# IoT_Greenhouse_V1_0_A_-_Esp32.net
KiCad netlist of a schematic drawn in Altium Designer
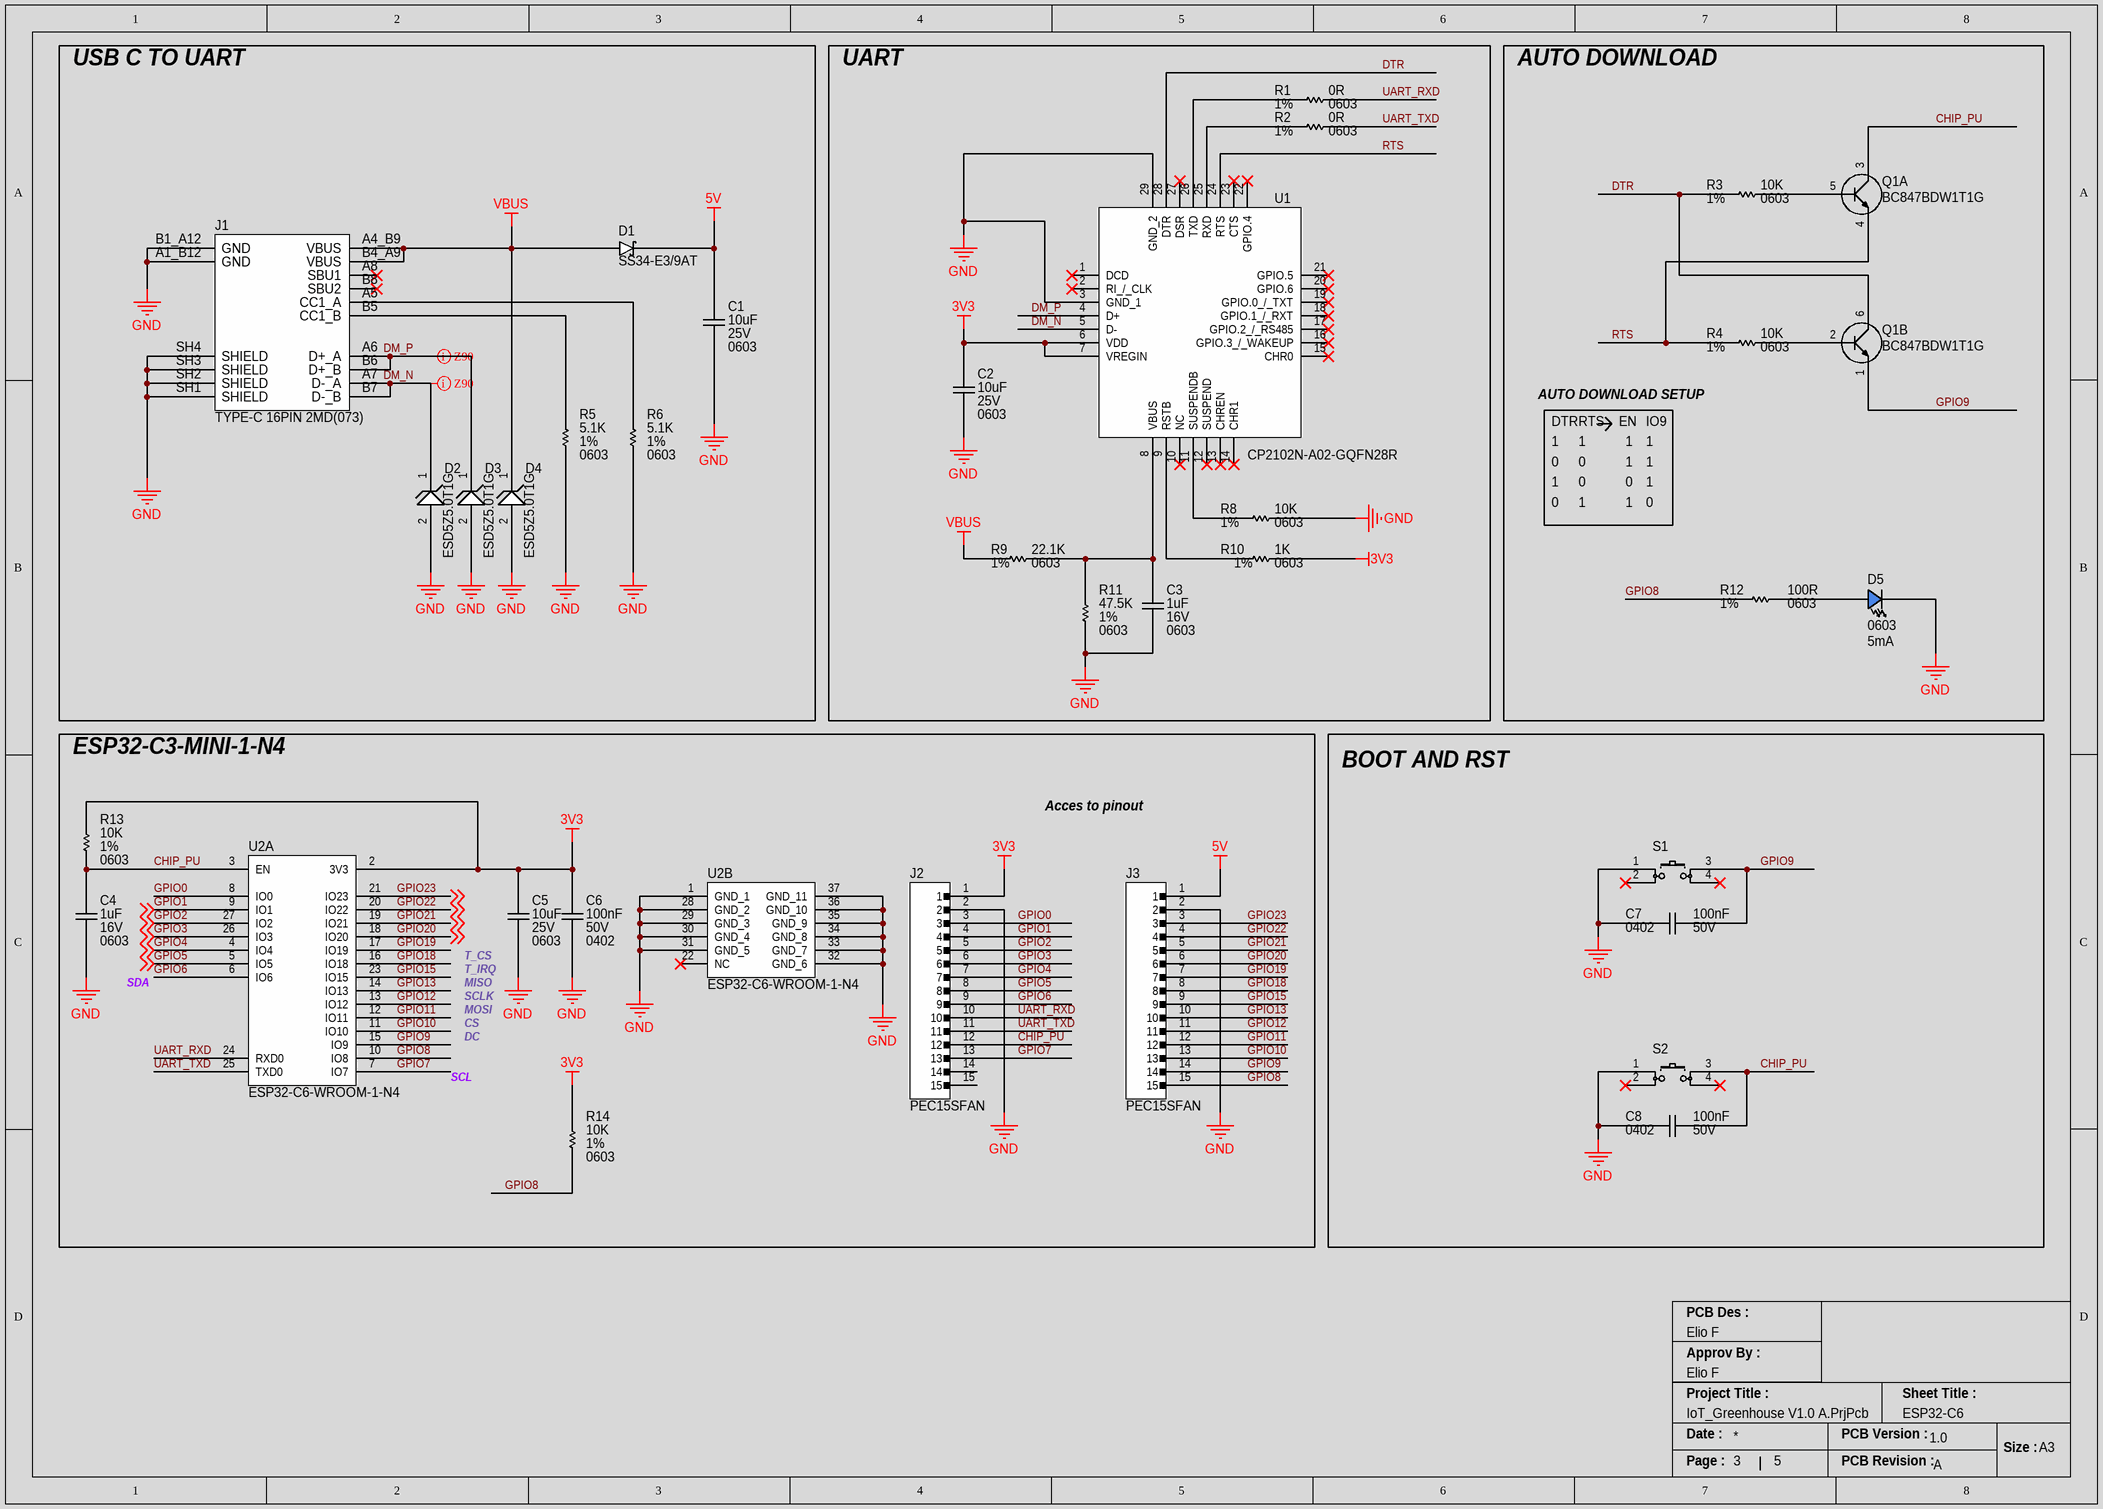
[diagram p0: IoT_Greenhouse V1.0 A - Esp32.SchDoc]

(export (version "E")
  (design (tool "Eeschema 10.0.6"))
  (components
    (comp (ref "C1")
      (value "GRM188R61E106MA73D")
      (footprint "CAP_0603_CAPC1608X08N")
      (description "Multilayer Ceramic Capacitor, 10 uF, 25 V, ± 20%, X5R, 0603 [1608 Metric]")
      (fields
        (field (name "MANUFACTURER") "Murata")
        (field (name "TOLERANCE") "20%")
        (field (name "CASE/PACKAGE") "0603")
        (field (name "CAPACITANCE") "10uF")
        (field (name "VOLTAGE RATING") "25V")
      )
      (libsource (lib "Electronic Devices_LIB") (part "CAP_10UF_25V_X5R_0603"))
    )
    (comp (ref "C2")
      (value "GRM188R61E106MA73D")
      (footprint "CAP_0603_CAPC1608X08N")
      (description "Multilayer Ceramic Capacitor, 10 uF, 25 V, ± 20%, X5R, 0603 [1608 Metric]")
      (fields
        (field (name "MANUFACTURER") "Murata")
        (field (name "TOLERANCE") "20%")
        (field (name "CASE/PACKAGE") "0603")
        (field (name "CAPACITANCE") "10uF")
        (field (name "VOLTAGE RATING") "25V")
      )
      (libsource (lib "Electronic Devices_LIB") (part "CAP_10UF_25V_X5R_0603"))
    )
    (comp (ref "C3")
      (value "CL10A105KO8NNNC")
      (footprint "CAP_0603_CAPC1608X08N")
      (description "CAP CER 1UF 16V X5R 0603")
      (fields
        (field (name "MANUFACTURER") "Samsung")
        (field (name "TOLERANCE") "10%")
        (field (name "VOLTAGE RATING") "16V")
        (field (name "CAPACITANCE") "1uF")
        (field (name "CASE/PACKAGE") "0603")
      )
      (libsource (lib "Electronic Devices_LIB") (part "CAP_1UF_16V_X5R_0603"))
    )
    (comp (ref "C4")
      (value "CL10A105KO8NNNC")
      (footprint "CAP_0603_CAPC1608X08N")
      (description "CAP CER 1UF 16V X5R 0603")
      (fields
        (field (name "MANUFACTURER") "Samsung")
        (field (name "TOLERANCE") "10%")
        (field (name "VOLTAGE RATING") "16V")
        (field (name "CAPACITANCE") "1uF")
        (field (name "CASE/PACKAGE") "0603")
      )
      (libsource (lib "Electronic Devices_LIB") (part "CAP_1UF_16V_X5R_0603"))
    )
    (comp (ref "C5")
      (value "GRM188R61E106MA73D")
      (footprint "CAP_0603_CAPC1608X08N")
      (description "Multilayer Ceramic Capacitor, 10 uF, 25 V, ± 20%, X5R, 0603 [1608 Metric]")
      (fields
        (field (name "MANUFACTURER") "Murata")
        (field (name "TOLERANCE") "20%")
        (field (name "CASE/PACKAGE") "0603")
        (field (name "CAPACITANCE") "10uF")
        (field (name "VOLTAGE RATING") "25V")
      )
      (libsource (lib "Electronic Devices_LIB") (part "CAP_10UF_25V_X5R_0603"))
    )
    (comp (ref "C6")
      (value "GRM155R71H104KE14D")
      (footprint "CAP_0402_CAPC1005X05N")
      (description "Multilayer Ceramic Capacitor, 0.1 uF, 16 V, ± 10%, X7R, 0402 [1005 Metric]")
      (fields
        (field (name "MANUFACTURER") "Murata")
        (field (name "TOLERANCE") "10%")
        (field (name "VOLTAGE RATING") "50V")
        (field (name "CAPACITANCE") "100nF")
        (field (name "CASE/PACKAGE") "0402")
      )
      (libsource (lib "Electronic Devices_LIB") (part "CAP_100NF_50V_X7R_0402"))
    )
    (comp (ref "C7")
      (value "GRM155R71H104KE14D")
      (footprint "CAP_0402_CAPC1005X05N")
      (description "Multilayer Ceramic Capacitor, 0.1 uF, 16 V, ± 10%, X7R, 0402 [1005 Metric]")
      (fields
        (field (name "MANUFACTURER") "Murata")
        (field (name "TOLERANCE") "10%")
        (field (name "VOLTAGE RATING") "50V")
        (field (name "CAPACITANCE") "100nF")
        (field (name "CASE/PACKAGE") "0402")
      )
      (libsource (lib "Electronic Devices_LIB") (part "CAP_100NF_50V_X7R_0402"))
    )
    (comp (ref "C8")
      (value "GRM155R71H104KE14D")
      (footprint "CAP_0402_CAPC1005X05N")
      (description "Multilayer Ceramic Capacitor, 0.1 uF, 16 V, ± 10%, X7R, 0402 [1005 Metric]")
      (fields
        (field (name "MANUFACTURER") "Murata")
        (field (name "TOLERANCE") "10%")
        (field (name "VOLTAGE RATING") "50V")
        (field (name "CAPACITANCE") "100nF")
        (field (name "CASE/PACKAGE") "0402")
      )
      (libsource (lib "Electronic Devices_LIB") (part "CAP_100NF_50V_X7R_0402"))
    )
    (comp (ref "D1")
      (value "SS34-E3/9AT")
      (footprint "DIO_Vishay_SMC_MFG")
      (description "Rectifier Diode, schottky, 40V V(Rrm), do-214Ab / Smc")
      (fields (field (name "MANUFACTURER") "Vishay Semiconductors"))
      (libsource (lib "Electronic Devices_LIB") (part "DIO_SCTKY_40V_3A"))
    )
    (comp (ref "D2")
      (value "ESD5Z5.0T1G")
      (footprint "SOD523_SODFL1608X70N")
      (description "ESD5Z Series 6.2 V 80 pF 5 Vrwm TVS and ESD Protection Diodes - SOD-523")
      (fields (field (name "MANUFACTURER") "ON Semiconductor"))
      (libsource (lib "Electronic Devices_LIB") (part "DIO_TVS_5V_ESD5Z5.0T1G"))
    )
    (comp (ref "D3")
      (value "ESD5Z5.0T1G")
      (footprint "SOD523_SODFL1608X70N")
      (description "ESD5Z Series 6.2 V 80 pF 5 Vrwm TVS and ESD Protection Diodes - SOD-523")
      (fields (field (name "MANUFACTURER") "ON Semiconductor"))
      (libsource (lib "Electronic Devices_LIB") (part "DIO_TVS_5V_ESD5Z5.0T1G"))
    )
    (comp (ref "D4")
      (value "ESD5Z5.0T1G")
      (footprint "SOD523_SODFL1608X70N")
      (description "ESD5Z Series 6.2 V 80 pF 5 Vrwm TVS and ESD Protection Diodes - SOD-523")
      (fields (field (name "MANUFACTURER") "ON Semiconductor"))
      (libsource (lib "Electronic Devices_LIB") (part "DIO_TVS_5V_ESD5Z5.0T1G"))
    )
    (comp (ref "D5")
      (value "LTST-C193TBKT-5A")
      (footprint "LED_0603-BLUE-0.75mm")
      (description "LED Uni-Color Blue 468nm 2-Pin Chip LED T/R")
      (fields
        (field (name "MANUFACTURER") "Vishay Lite-On")
        (field (name "CASE CODE (IMPERIAL)") "0603")
        (field (name "TEST CURRENT") "5mA")
      )
      (libsource (lib "Electronic Devices_LIB") (part "LED_DIO_BLUE_5mA_0603"))
    )
    (comp (ref "J1")
      (value "TYPE-C 16PIN 2MD(073)")
      (footprint "CONN_USB_C_16P")
      (description "5A 1 Surface Mount 16P Female -25℃~+85℃ Type-C SMD USB Connectors ROHS")
      (fields (field (name "MANUFACTURER") "SHOU HAN"))
      (libsource (lib "Electronic Devices_LIB") (part "CONN_USB_TYPEC_2.0_16P_TYPE-C 16PIN 2MD(073)"))
    )
    (comp (ref "J2")
      (value "PEC15SFAN")
      (footprint "HEADER_MALE_15P")
      (description "CONN HEADER .100 SINGL STR 15POS")
      (fields (field (name "MANUFACTURER") "Sullins"))
      (libsource (lib "Electronic Devices_LIB") (part "CONN_HEADER_MALE_15P_2.54mm"))
    )
    (comp (ref "J3")
      (value "PEC15SFAN")
      (footprint "HEADER_MALE_15P")
      (description "CONN HEADER .100 SINGL STR 15POS")
      (fields (field (name "MANUFACTURER") "Sullins"))
      (libsource (lib "Electronic Devices_LIB") (part "CONN_HEADER_MALE_15P_2.54mm"))
    )
    (comp (ref "Q1")
      (value "BC847BDW1T1G")
      (footprint "TRANS_BJT_SOT65P210X110-6N")
      (description "ON Semi BC847BDW1T1G Dual NPN Bipolar Transistor; 0.1 A; 45 V; 6-Pin SC-88")
      (fields (field (name "MANUFACTURER") "ON Semiconductor"))
      (libsource (lib "Electronic Devices_LIB") (part "TRANS_BIPOLAR_NPN_BC847BDW1T1G"))
    )
    (comp (ref "R1")
      (value "RC0603FR-070RL")
      (footprint "RES_0603_RESC1608X04N")
      (description "RC Series 0603 0.1 W 0 Ohm Jumper Surface Mount Thick Film Chip Resistor")
      (fields
        (field (name "MANUFACTURER") "Yageo")
        (field (name "TOLERANCE") "1%")
        (field (name "RESISTANCE") "0R")
        (field (name "CASE CODE (IMPERIAL)") "0603")
      )
      (libsource (lib "Electronic Devices_LIB") (part "RES_0R_1%_100mW_0603"))
    )
    (comp (ref "R2")
      (value "RC0603FR-070RL")
      (footprint "RES_0603_RESC1608X04N")
      (description "RC Series 0603 0.1 W 0 Ohm Jumper Surface Mount Thick Film Chip Resistor")
      (fields
        (field (name "MANUFACTURER") "Yageo")
        (field (name "TOLERANCE") "1%")
        (field (name "RESISTANCE") "0R")
        (field (name "CASE CODE (IMPERIAL)") "0603")
      )
      (libsource (lib "Electronic Devices_LIB") (part "RES_0R_1%_100mW_0603"))
    )
    (comp (ref "R3")
      (value "AC0603FR-1010KL")
      (footprint "RES_0603_RESC1608X04N")
      (description "Chip Resistor Automotive Grade Thick Film 0603 10kOhm 1% Paper T/R")
      (fields
        (field (name "MANUFACTURER") "Yageo")
        (field (name "RESISTANCE") "10K")
        (field (name "TOLERANCE") "1%")
        (field (name "CASE/PACKAGE") "0603")
      )
      (libsource (lib "Electronic Devices_LIB") (part "RES_10K_1%_100mW_0603"))
    )
    (comp (ref "R4")
      (value "AC0603FR-1010KL")
      (footprint "RES_0603_RESC1608X04N")
      (description "Chip Resistor Automotive Grade Thick Film 0603 10kOhm 1% Paper T/R")
      (fields
        (field (name "MANUFACTURER") "Yageo")
        (field (name "RESISTANCE") "10K")
        (field (name "TOLERANCE") "1%")
        (field (name "CASE/PACKAGE") "0603")
      )
      (libsource (lib "Electronic Devices_LIB") (part "RES_10K_1%_100mW_0603"))
    )
    (comp (ref "R5")
      (value "RC0603FR-075K1L")
      (footprint "RES_0603_RESC1608X04N")
      (description "SMD Chip Resistor, 5.1 kOhm, ± 1%, 100 mW, 0603 [1608 Metric], Thick Film, General Purpose")
      (fields
        (field (name "MANUFACTURER") "Yageo")
        (field (name "TOLERANCE") "1%")
        (field (name "RESISTANCE") "5.1K")
        (field (name "CASE/PACKAGE") "0603")
      )
      (libsource (lib "Electronic Devices_LIB") (part "RES_5.1K_1%_100mW_0603"))
    )
    (comp (ref "R6")
      (value "RC0603FR-075K1L")
      (footprint "RES_0603_RESC1608X04N")
      (description "SMD Chip Resistor, 5.1 kOhm, ± 1%, 100 mW, 0603 [1608 Metric], Thick Film, General Purpose")
      (fields
        (field (name "MANUFACTURER") "Yageo")
        (field (name "TOLERANCE") "1%")
        (field (name "RESISTANCE") "5.1K")
        (field (name "CASE/PACKAGE") "0603")
      )
      (libsource (lib "Electronic Devices_LIB") (part "RES_5.1K_1%_100mW_0603"))
    )
    (comp (ref "R8")
      (value "AC0603FR-1010KL")
      (footprint "RES_0603_RESC1608X04N")
      (description "Chip Resistor Automotive Grade Thick Film 0603 10kOhm 1% Paper T/R")
      (fields
        (field (name "MANUFACTURER") "Yageo")
        (field (name "RESISTANCE") "10K")
        (field (name "TOLERANCE") "1%")
        (field (name "CASE/PACKAGE") "0603")
      )
      (libsource (lib "Electronic Devices_LIB") (part "RES_10K_1%_100mW_0603"))
    )
    (comp (ref "R9")
      (value "RC0603FR-0722K1L")
      (footprint "RES_0603_RESC1608X04N")
      (description "SMD Chip Resistor, 22.1 kOhm, ± 1%, 100 mW, 0603 [1608 Metric], Thick Film, General Purpose")
      (fields
        (field (name "MANUFACTURER") "Yageo")
        (field (name "RESISTANCE") "22.1K")
        (field (name "TOLERANCE") "1%")
        (field (name "CASE/PACKAGE") "0603")
      )
      (libsource (lib "Electronic Devices_LIB") (part "RES_22.1K_1%_100mW_0603"))
    )
    (comp (ref "R10")
      (value "AC0603FR-101KL")
      (footprint "RES_0603_RESC1608X04N")
      (description "Chip Resistor Automotive Grade Thick Film 0603 1kOhm 1% Paper T/R")
      (fields
        (field (name "MANUFACTURER") "Yageo")
        (field (name "RESISTANCE") "1K")
        (field (name "TOLERANCE") "1%")
        (field (name "CASE/PACKAGE") "0603")
      )
      (libsource (lib "Electronic Devices_LIB") (part "RES_1K_1%_100mW_0603"))
    )
    (comp (ref "R11")
      (value "AC0603FR-0747K5L")
      (footprint "RES_0603_RESC1608X04N")
      (description "SMD Chip Resistor, 47.5 kOhm, ± 1%, 100 mW, 0603 [1608 Metric], Thick Film, General Purpose")
      (fields
        (field (name "MANUFACTURER") "Yageo")
        (field (name "TOLERANCE") "1%")
        (field (name "RESISTANCE") "47.5K")
        (field (name "CASE/PACKAGE") "0603")
      )
      (libsource (lib "Electronic Devices_LIB") (part "RES_47.5K_1%_100mW_0603"))
    )
    (comp (ref "R12")
      (value "ERJ3EKF1000V")
      (footprint "CAP_0603_CAPC1608X08N")
      (description "Res Thick Film 0603 100 Ohm 1% 1/10W ±100ppm/°C Molded SMD Punched Carrier T/R")
      (fields
        (field (name "MANUFACTURER") "Panasonic")
        (field (name "CASE CODE (IMPERIAL)") "0603")
        (field (name "TOLERANCE") "1%")
        (field (name "RESISTANCE") "100R")
      )
      (libsource (lib "Electronic Devices_LIB") (part "RES_100R_1%_100MW_0603"))
    )
    (comp (ref "R13")
      (value "AC0603FR-1010KL")
      (footprint "RES_0603_RESC1608X04N")
      (description "Chip Resistor Automotive Grade Thick Film 0603 10kOhm 1% Paper T/R")
      (fields
        (field (name "MANUFACTURER") "Yageo")
        (field (name "RESISTANCE") "10K")
        (field (name "TOLERANCE") "1%")
        (field (name "CASE/PACKAGE") "0603")
      )
      (libsource (lib "Electronic Devices_LIB") (part "RES_10K_1%_100mW_0603"))
    )
    (comp (ref "R14")
      (value "AC0603FR-1010KL")
      (footprint "RES_0603_RESC1608X04N")
      (description "Chip Resistor Automotive Grade Thick Film 0603 10kOhm 1% Paper T/R")
      (fields
        (field (name "MANUFACTURER") "Yageo")
        (field (name "RESISTANCE") "10K")
        (field (name "TOLERANCE") "1%")
        (field (name "CASE/PACKAGE") "0603")
      )
      (libsource (lib "Electronic Devices_LIB") (part "RES_10K_1%_100mW_0603"))
    )
    (comp (ref "S1")
      (value "PTS526SK15SMTR2LFS")
      (footprint "SWT_NO_PTS526SK15SMTR2LFS")
      (description "Switch Tactile N.O. SPST Round Button Gull Wing 0.05A 12VDC 200000Cycles 2.55N SMD T/R")
      (fields (field (name "MANUFACTURER") "ITT C&K"))
      (libsource (lib "Electronic Devices_LIB") (part "SWITCH_NO_SPST_0.05A"))
    )
    (comp (ref "S2")
      (value "PTS526SK15SMTR2LFS")
      (footprint "SWT_NO_PTS526SK15SMTR2LFS")
      (description "Switch Tactile N.O. SPST Round Button Gull Wing 0.05A 12VDC 200000Cycles 2.55N SMD T/R")
      (fields (field (name "MANUFACTURER") "ITT C&K"))
      (libsource (lib "Electronic Devices_LIB") (part "SWITCH_NO_SPST_0.05A"))
    )
    (comp (ref "U1")
      (value "CP2102N-A02-GQFN28R")
      (footprint "IC_BRIDGE_UART_QFN50P500X500X80-29N-D")
      (description "Full Speed USB to UART Bridge USB 2.0 3.3V T/R Automotive 28-Pin QFN EP")
      (fields (field (name "MANUFACTURER") "Silicon Labs"))
      (libsource (lib "Electronic Devices_LIB") (part "IC_BRIDGE_UART_CP2102N-A02-GQFN28R"))
    )
    (comp (ref "U2")
      (value "ESP32-C6-WROOM-1-N4")
      (footprint "IC_MODULE_ESP32C6WROOM1N4")
      (description "ESP32-C6-WROOM-1-N4 Engineering Module - 4 MB Quad SPI Flash")
      (fields (field (name "MANUFACTURER") "Espressif Systems"))
      (libsource (lib "Electronic Devices_LIB") (part "IC_MODULE_ESP32-C6-WROOM-1-N4"))
    )
  )
  (nets
    (net (code "1") (name "/CHIP_PU") (class "Default")
      (node (ref "C4") (pin "2") (pinfunction "2_2") (pintype "passive"))
      (node (ref "C8") (pin "1") (pinfunction "1_1") (pintype "passive"))
      (node (ref "J2") (pin "12") (pinfunction "12_12") (pintype "passive"))
      (node (ref "Q1") (pin "3") (pinfunction "COLLECTOR_1_3") (pintype "passive"))
      (node (ref "R13") (pin "2") (pinfunction "2_2") (pintype "passive"))
      (node (ref "S2") (pin "3") (pinfunction "NO1_3") (pintype "passive"))
      (node (ref "U2") (pin "3") (pinfunction "EN_3") (pintype "passive"))
    )
    (net (code "2") (name "/DM_N") (class "Default")
      (node (ref "D2") (pin "1") (pinfunction "K_1") (pintype "passive"))
      (node (ref "J1") (pin "A7") (pinfunction "D-_A_A7") (pintype "passive"))
      (node (ref "J1") (pin "B7") (pinfunction "D-_B_B7") (pintype "passive"))
      (node (ref "U1") (pin "5") (pinfunction "D-_5") (pintype "passive"))
    )
    (net (code "3") (name "/DM_P") (class "Default")
      (node (ref "D3") (pin "1") (pinfunction "K_1") (pintype "passive"))
      (node (ref "J1") (pin "A6") (pinfunction "D+_A_A6") (pintype "passive"))
      (node (ref "J1") (pin "B6") (pinfunction "D+_B_B6") (pintype "passive"))
      (node (ref "U1") (pin "4") (pinfunction "D+_4") (pintype "passive"))
    )
    (net (code "4") (name "/DTR") (class "Default")
      (node (ref "Q1") (pin "6") (pinfunction "COLLECTOR_2_6") (pintype "passive"))
      (node (ref "R3") (pin "2") (pinfunction "2_2") (pintype "passive"))
      (node (ref "U1") (pin "28") (pinfunction "DTR_28") (pintype "passive"))
    )
    (net (code "5") (name "/GPIO0") (class "Default")
      (node (ref "J2") (pin "3") (pinfunction "3_3") (pintype "passive"))
      (node (ref "U2") (pin "8") (pinfunction "IO0_8") (pintype "passive"))
    )
    (net (code "6") (name "/GPIO1") (class "Default")
      (node (ref "J2") (pin "4") (pinfunction "4_4") (pintype "passive"))
      (node (ref "J2") (pin "5") (pinfunction "5_5") (pintype "passive"))
      (node (ref "J2") (pin "6") (pinfunction "6_6") (pintype "passive"))
      (node (ref "J2") (pin "7") (pinfunction "7_7") (pintype "passive"))
      (node (ref "J2") (pin "8") (pinfunction "8_8") (pintype "passive"))
      (node (ref "J3") (pin "3") (pinfunction "3_3") (pintype "passive"))
      (node (ref "J3") (pin "4") (pinfunction "4_4") (pintype "passive"))
      (node (ref "J3") (pin "5") (pinfunction "5_5") (pintype "passive"))
      (node (ref "J3") (pin "6") (pinfunction "6_6") (pintype "passive"))
      (node (ref "U2") (pin "18") (pinfunction "IO20_18") (pintype "passive"))
      (node (ref "U2") (pin "19") (pinfunction "IO21_19") (pintype "passive"))
      (node (ref "U2") (pin "20") (pinfunction "IO22_20") (pintype "passive"))
      (node (ref "U2") (pin "21") (pinfunction "IO23_21") (pintype "passive"))
      (node (ref "U2") (pin "26") (pinfunction "IO3_26") (pintype "passive"))
      (node (ref "U2") (pin "27") (pinfunction "IO2_27") (pintype "passive"))
      (node (ref "U2") (pin "4") (pinfunction "IO4_4") (pintype "passive"))
      (node (ref "U2") (pin "5") (pinfunction "IO5_5") (pintype "passive"))
      (node (ref "U2") (pin "9") (pinfunction "IO1_9") (pintype "passive"))
    )
    (net (code "7") (name "/GPIO6") (class "Default")
      (node (ref "J2") (pin "9") (pinfunction "9_9") (pintype "passive"))
      (node (ref "U2") (pin "6") (pinfunction "IO6_6") (pintype "passive"))
    )
    (net (code "8") (name "/GPIO7") (class "Default")
      (node (ref "J2") (pin "13") (pinfunction "13_13") (pintype "passive"))
      (node (ref "U2") (pin "7") (pinfunction "IO7_7") (pintype "passive"))
    )
    (net (code "9") (name "/GPIO8") (class "Default")
      (node (ref "J3") (pin "15") (pinfunction "15_15") (pintype "passive"))
      (node (ref "R12") (pin "1") (pinfunction "1_1") (pintype "passive"))
      (node (ref "R14") (pin "2") (pinfunction "2_2") (pintype "passive"))
      (node (ref "U2") (pin "10") (pinfunction "IO8_10") (pintype "passive"))
    )
    (net (code "10") (name "/GPIO9") (class "Default")
      (node (ref "C7") (pin "1") (pinfunction "1_1") (pintype "passive"))
      (node (ref "J3") (pin "14") (pinfunction "14_14") (pintype "passive"))
      (node (ref "Q1") (pin "1") (pinfunction "EMITTER_2_1") (pintype "passive"))
      (node (ref "S1") (pin "3") (pinfunction "NO1_3") (pintype "passive"))
      (node (ref "U2") (pin "15") (pinfunction "IO9_15") (pintype "passive"))
    )
    (net (code "11") (name "/GPIO10") (class "Default")
      (node (ref "J3") (pin "13") (pinfunction "13_13") (pintype "passive"))
      (node (ref "U2") (pin "11") (pinfunction "IO10_11") (pintype "passive"))
    )
    (net (code "12") (name "/GPIO11") (class "Default")
      (node (ref "J3") (pin "12") (pinfunction "12_12") (pintype "passive"))
      (node (ref "U2") (pin "12") (pinfunction "IO11_12") (pintype "passive"))
    )
    (net (code "13") (name "/GPIO12") (class "Default")
      (node (ref "J3") (pin "11") (pinfunction "11_11") (pintype "passive"))
      (node (ref "U2") (pin "13") (pinfunction "IO12_13") (pintype "passive"))
    )
    (net (code "14") (name "/GPIO13") (class "Default")
      (node (ref "J3") (pin "10") (pinfunction "10_10") (pintype "passive"))
      (node (ref "U2") (pin "14") (pinfunction "IO13_14") (pintype "passive"))
    )
    (net (code "15") (name "/GPIO15") (class "Default")
      (node (ref "J3") (pin "9") (pinfunction "9_9") (pintype "passive"))
      (node (ref "U2") (pin "23") (pinfunction "IO15_23") (pintype "passive"))
    )
    (net (code "16") (name "/GPIO18") (class "Default")
      (node (ref "J3") (pin "8") (pinfunction "8_8") (pintype "passive"))
      (node (ref "U2") (pin "16") (pinfunction "IO18_16") (pintype "passive"))
    )
    (net (code "17") (name "/GPIO19") (class "Default")
      (node (ref "J3") (pin "7") (pinfunction "7_7") (pintype "passive"))
      (node (ref "U2") (pin "17") (pinfunction "IO19_17") (pintype "passive"))
    )
    (net (code "18") (name "/RTS") (class "Default")
      (node (ref "Q1") (pin "4") (pinfunction "EMITTER_1_4") (pintype "passive"))
      (node (ref "R4") (pin "2") (pinfunction "2_2") (pintype "passive"))
      (node (ref "U1") (pin "24") (pinfunction "RTS_24") (pintype "passive"))
    )
    (net (code "19") (name "/UART_RXD") (class "Default")
      (node (ref "J2") (pin "10") (pinfunction "10_10") (pintype "passive"))
      (node (ref "R1") (pin "1") (pinfunction "1_1") (pintype "passive"))
      (node (ref "U2") (pin "24") (pinfunction "RXD0_24") (pintype "passive"))
    )
    (net (code "20") (name "/UART_TXD") (class "Default")
      (node (ref "J2") (pin "11") (pinfunction "11_11") (pintype "passive"))
      (node (ref "R2") (pin "1") (pinfunction "1_1") (pintype "passive"))
      (node (ref "U2") (pin "25") (pinfunction "TXD0_25") (pintype "passive"))
    )
    (net (code "21") (name "3V3") (class "Default")
      (node (ref "C2") (pin "2") (pinfunction "2_2") (pintype "passive"))
      (node (ref "C5") (pin "2") (pinfunction "2_2") (pintype "passive"))
      (node (ref "C6") (pin "2") (pinfunction "2_2") (pintype "passive"))
      (node (ref "J2") (pin "1") (pinfunction "1_1") (pintype "passive"))
      (node (ref "R10") (pin "2") (pinfunction "2_2") (pintype "passive"))
      (node (ref "R13") (pin "1") (pinfunction "1_1") (pintype "passive"))
      (node (ref "R14") (pin "1") (pinfunction "1_1") (pintype "passive"))
      (node (ref "U1") (pin "6") (pinfunction "VDD_6") (pintype "passive"))
      (node (ref "U1") (pin "7") (pinfunction "VREGIN_7") (pintype "passive"))
      (node (ref "U2") (pin "2") (pinfunction "3V3_2") (pintype "passive"))
    )
    (net (code "22") (name "5V") (class "Default")
      (node (ref "C1") (pin "2") (pinfunction "2_2") (pintype "passive"))
      (node (ref "D1") (pin "1") (pinfunction "K_1") (pintype "passive"))
      (node (ref "J3") (pin "1") (pinfunction "1_1") (pintype "passive"))
    )
    (net (code "23") (name "GND") (class "Default")
      (node (ref "C1") (pin "1") (pinfunction "1_1") (pintype "passive"))
      (node (ref "C2") (pin "1") (pinfunction "1_1") (pintype "passive"))
      (node (ref "C3") (pin "1") (pinfunction "1_1") (pintype "passive"))
      (node (ref "C4") (pin "1") (pinfunction "1_1") (pintype "passive"))
      (node (ref "C5") (pin "1") (pinfunction "1_1") (pintype "passive"))
      (node (ref "C6") (pin "1") (pinfunction "1_1") (pintype "passive"))
      (node (ref "C7") (pin "2") (pinfunction "2_2") (pintype "passive"))
      (node (ref "C8") (pin "2") (pinfunction "2_2") (pintype "passive"))
      (node (ref "D2") (pin "2") (pinfunction "A_2") (pintype "passive"))
      (node (ref "D3") (pin "2") (pinfunction "A_2") (pintype "passive"))
      (node (ref "D4") (pin "2") (pinfunction "A_2") (pintype "passive"))
      (node (ref "D5") (pin "1") (pinfunction "C_1") (pintype "passive"))
      (node (ref "J1") (pin "A1_B12") (pinfunction "GND_A1_B12") (pintype "power_in"))
      (node (ref "J1") (pin "B1_A12") (pinfunction "GND_B1_A12") (pintype "power_in"))
      (node (ref "J1") (pin "SH1") (pinfunction "SHIELD_SH1") (pintype "passive"))
      (node (ref "J1") (pin "SH2") (pinfunction "SHIELD_SH2") (pintype "passive"))
      (node (ref "J1") (pin "SH3") (pinfunction "SHIELD_SH3") (pintype "passive"))
      (node (ref "J1") (pin "SH4") (pinfunction "SHIELD_SH4") (pintype "passive"))
      (node (ref "J2") (pin "2") (pinfunction "2_2") (pintype "passive"))
      (node (ref "J3") (pin "2") (pinfunction "2_2") (pintype "passive"))
      (node (ref "R11") (pin "1") (pinfunction "1_1") (pintype "passive"))
      (node (ref "R5") (pin "1") (pinfunction "1_1") (pintype "passive"))
      (node (ref "R6") (pin "1") (pinfunction "1_1") (pintype "passive"))
      (node (ref "R8") (pin "2") (pinfunction "2_2") (pintype "passive"))
      (node (ref "S1") (pin "1") (pinfunction "COM_1_1") (pintype "passive"))
      (node (ref "S2") (pin "1") (pinfunction "COM_1_1") (pintype "passive"))
      (node (ref "U1") (pin "29") (pinfunction "GND_2_29") (pintype "passive"))
      (node (ref "U1") (pin "3") (pinfunction "GND_1_3") (pintype "passive"))
      (node (ref "U2") (pin "1") (pinfunction "GND_1_1") (pintype "passive"))
      (node (ref "U2") (pin "28") (pinfunction "GND_2_28") (pintype "passive"))
      (node (ref "U2") (pin "29") (pinfunction "GND_3_29") (pintype "passive"))
      (node (ref "U2") (pin "30") (pinfunction "GND_4_30") (pintype "passive"))
      (node (ref "U2") (pin "31") (pinfunction "GND_5_31") (pintype "passive"))
      (node (ref "U2") (pin "32") (pinfunction "GND_6_32") (pintype "passive"))
      (node (ref "U2") (pin "33") (pinfunction "GND_7_33") (pintype "passive"))
      (node (ref "U2") (pin "34") (pinfunction "GND_8_34") (pintype "passive"))
      (node (ref "U2") (pin "35") (pinfunction "GND_9_35") (pintype "passive"))
      (node (ref "U2") (pin "36") (pinfunction "GND_10_36") (pintype "passive"))
      (node (ref "U2") (pin "37") (pinfunction "GND_11_37") (pintype "passive"))
    )
    (net (code "24") (name "Net-(D5-A)") (class "Default")
      (node (ref "D5") (pin "2") (pinfunction "A_2") (pintype "passive"))
      (node (ref "R12") (pin "2") (pinfunction "2_2") (pintype "passive"))
    )
    (net (code "25") (name "Net-(J1-CC1_A)") (class "Default")
      (node (ref "J1") (pin "A5") (pinfunction "CC1_A_A5") (pintype "passive"))
      (node (ref "R6") (pin "2") (pinfunction "2_2") (pintype "passive"))
    )
    (net (code "26") (name "Net-(J1-CC1_B)") (class "Default")
      (node (ref "J1") (pin "B5") (pinfunction "CC1_B_B5") (pintype "passive"))
      (node (ref "R5") (pin "2") (pinfunction "2_2") (pintype "passive"))
    )
    (net (code "27") (name "Net-(Q1A-BASE_1)") (class "Default")
      (node (ref "Q1") (pin "5") (pinfunction "BASE_1_5") (pintype "passive"))
      (node (ref "R3") (pin "1") (pinfunction "1_1") (pintype "passive"))
    )
    (net (code "28") (name "Net-(Q1B-BASE_2)") (class "Default")
      (node (ref "Q1") (pin "2") (pinfunction "BASE_2_2") (pintype "passive"))
      (node (ref "R4") (pin "1") (pinfunction "1_1") (pintype "passive"))
    )
    (net (code "29") (name "Net-(U1-RSTB)") (class "Default")
      (node (ref "R10") (pin "1") (pinfunction "1_1") (pintype "passive"))
      (node (ref "U1") (pin "9") (pinfunction "RSTB_9") (pintype "passive"))
    )
    (net (code "30") (name "Net-(U1-RXD)") (class "Default")
      (node (ref "R2") (pin "2") (pinfunction "2_2") (pintype "passive"))
      (node (ref "U1") (pin "25") (pinfunction "RXD_25") (pintype "passive"))
    )
    (net (code "31") (name "Net-(U1-SUSPENDB)") (class "Default")
      (node (ref "R8") (pin "1") (pinfunction "1_1") (pintype "passive"))
      (node (ref "U1") (pin "11") (pinfunction "SUSPENDB_11") (pintype "passive"))
    )
    (net (code "32") (name "Net-(U1-TXD)") (class "Default")
      (node (ref "R1") (pin "2") (pinfunction "2_2") (pintype "passive"))
      (node (ref "U1") (pin "26") (pinfunction "TXD_26") (pintype "passive"))
    )
    (net (code "33") (name "Net-(U1-VBUS)") (class "Default")
      (node (ref "C3") (pin "2") (pinfunction "2_2") (pintype "passive"))
      (node (ref "R11") (pin "2") (pinfunction "2_2") (pintype "passive"))
      (node (ref "R9") (pin "2") (pinfunction "2_2") (pintype "passive"))
      (node (ref "U1") (pin "8") (pinfunction "VBUS_8") (pintype "passive"))
    )
    (net (code "34") (name "VBUS") (class "Default")
      (node (ref "D1") (pin "2") (pinfunction "A_2") (pintype "passive"))
      (node (ref "D4") (pin "1") (pinfunction "K_1") (pintype "passive"))
      (node (ref "J1") (pin "A4_B9") (pinfunction "VBUS_A4_B9") (pintype "power_in"))
      (node (ref "J1") (pin "B4_A9") (pinfunction "VBUS_B4_A9") (pintype "power_in"))
      (node (ref "R9") (pin "1") (pinfunction "1_1") (pintype "passive"))
    )
    (net (code "35") (name "unconnected-(J1-SBU1-PadA8)") (class "Default")
      (node (ref "J1") (pin "A8") (pinfunction "SBU1_A8") (pintype "passive+no_connect"))
    )
    (net (code "36") (name "unconnected-(J1-SBU2-PadB8)") (class "Default")
      (node (ref "J1") (pin "B8") (pinfunction "SBU2_B8") (pintype "passive+no_connect"))
    )
    (net (code "37") (name "unconnected-(J2-Pad14)") (class "Default")
      (node (ref "J2") (pin "14") (pinfunction "14_14") (pintype "passive"))
    )
    (net (code "38") (name "unconnected-(J2-Pad15)") (class "Default")
      (node (ref "J2") (pin "15") (pinfunction "15_15") (pintype "passive"))
    )
    (net (code "39") (name "unconnected-(S1-COM2-Pad2)") (class "Default")
      (node (ref "S1") (pin "2") (pinfunction "COM2_2") (pintype "passive+no_connect"))
    )
    (net (code "40") (name "unconnected-(S1-NO2-Pad4)") (class "Default")
      (node (ref "S1") (pin "4") (pinfunction "NO2_4") (pintype "passive+no_connect"))
    )
    (net (code "41") (name "unconnected-(S2-COM2-Pad2)") (class "Default")
      (node (ref "S2") (pin "2") (pinfunction "COM2_2") (pintype "passive+no_connect"))
    )
    (net (code "42") (name "unconnected-(S2-NO2-Pad4)") (class "Default")
      (node (ref "S2") (pin "4") (pinfunction "NO2_4") (pintype "passive+no_connect"))
    )
    (net (code "43") (name "unconnected-(U1-CHR0-Pad15)") (class "Default")
      (node (ref "U1") (pin "15") (pinfunction "CHR0_15") (pintype "passive+no_connect"))
    )
    (net (code "44") (name "unconnected-(U1-CHR1-Pad14)") (class "Default")
      (node (ref "U1") (pin "14") (pinfunction "CHR1_14") (pintype "passive+no_connect"))
    )
    (net (code "45") (name "unconnected-(U1-CHREN-Pad13)") (class "Default")
      (node (ref "U1") (pin "13") (pinfunction "CHREN_13") (pintype "passive+no_connect"))
    )
    (net (code "46") (name "unconnected-(U1-CTS-Pad23)") (class "Default")
      (node (ref "U1") (pin "23") (pinfunction "CTS_23") (pintype "passive+no_connect"))
    )
    (net (code "47") (name "unconnected-(U1-DCD-Pad1)") (class "Default")
      (node (ref "U1") (pin "1") (pinfunction "DCD_1") (pintype "passive+no_connect"))
    )
    (net (code "48") (name "unconnected-(U1-DSR-Pad27)") (class "Default")
      (node (ref "U1") (pin "27") (pinfunction "DSR_27") (pintype "passive+no_connect"))
    )
    (net (code "49") (name "unconnected-(U1-GPIO.0_{slash}_TXT-Pad19)") (class "Default")
      (node (ref "U1") (pin "19") (pinfunction "GPIO.0_/_TXT_19") (pintype "passive+no_connect"))
    )
    (net (code "50") (name "unconnected-(U1-GPIO.1_{slash}_RXT-Pad18)") (class "Default")
      (node (ref "U1") (pin "18") (pinfunction "GPIO.1_/_RXT_18") (pintype "passive+no_connect"))
    )
    (net (code "51") (name "unconnected-(U1-GPIO.2_{slash}_RS485-Pad17)") (class "Default")
      (node (ref "U1") (pin "17") (pinfunction "GPIO.2_/_RS485_17") (pintype "passive+no_connect"))
    )
    (net (code "52") (name "unconnected-(U1-GPIO.3_{slash}_WAKEUP-Pad16)") (class "Default")
      (node (ref "U1") (pin "16") (pinfunction "GPIO.3_/_WAKEUP_16") (pintype "passive+no_connect"))
    )
    (net (code "53") (name "unconnected-(U1-GPIO.4-Pad22)") (class "Default")
      (node (ref "U1") (pin "22") (pinfunction "GPIO.4_22") (pintype "passive+no_connect"))
    )
    (net (code "54") (name "unconnected-(U1-GPIO.5-Pad21)") (class "Default")
      (node (ref "U1") (pin "21") (pinfunction "GPIO.5_21") (pintype "passive+no_connect"))
    )
    (net (code "55") (name "unconnected-(U1-GPIO.6-Pad20)") (class "Default")
      (node (ref "U1") (pin "20") (pinfunction "GPIO.6_20") (pintype "passive+no_connect"))
    )
    (net (code "56") (name "unconnected-(U1-NC-Pad10)") (class "Default")
      (node (ref "U1") (pin "10") (pinfunction "NC_10") (pintype "passive+no_connect"))
    )
    (net (code "57") (name "unconnected-(U1-RI_{slash}_CLK-Pad2)") (class "Default")
      (node (ref "U1") (pin "2") (pinfunction "RI_/_CLK_2") (pintype "passive+no_connect"))
    )
    (net (code "58") (name "unconnected-(U1-SUSPEND-Pad12)") (class "Default")
      (node (ref "U1") (pin "12") (pinfunction "SUSPEND_12") (pintype "passive+no_connect"))
    )
    (net (code "59") (name "unconnected-(U2B-NC-Pad22)") (class "Default")
      (node (ref "U2") (pin "22") (pinfunction "NC_22") (pintype "passive+no_connect"))
    )
  )
)
